# Esquematico.net
KiCad netlist of a schematic drawn in Altium Designer
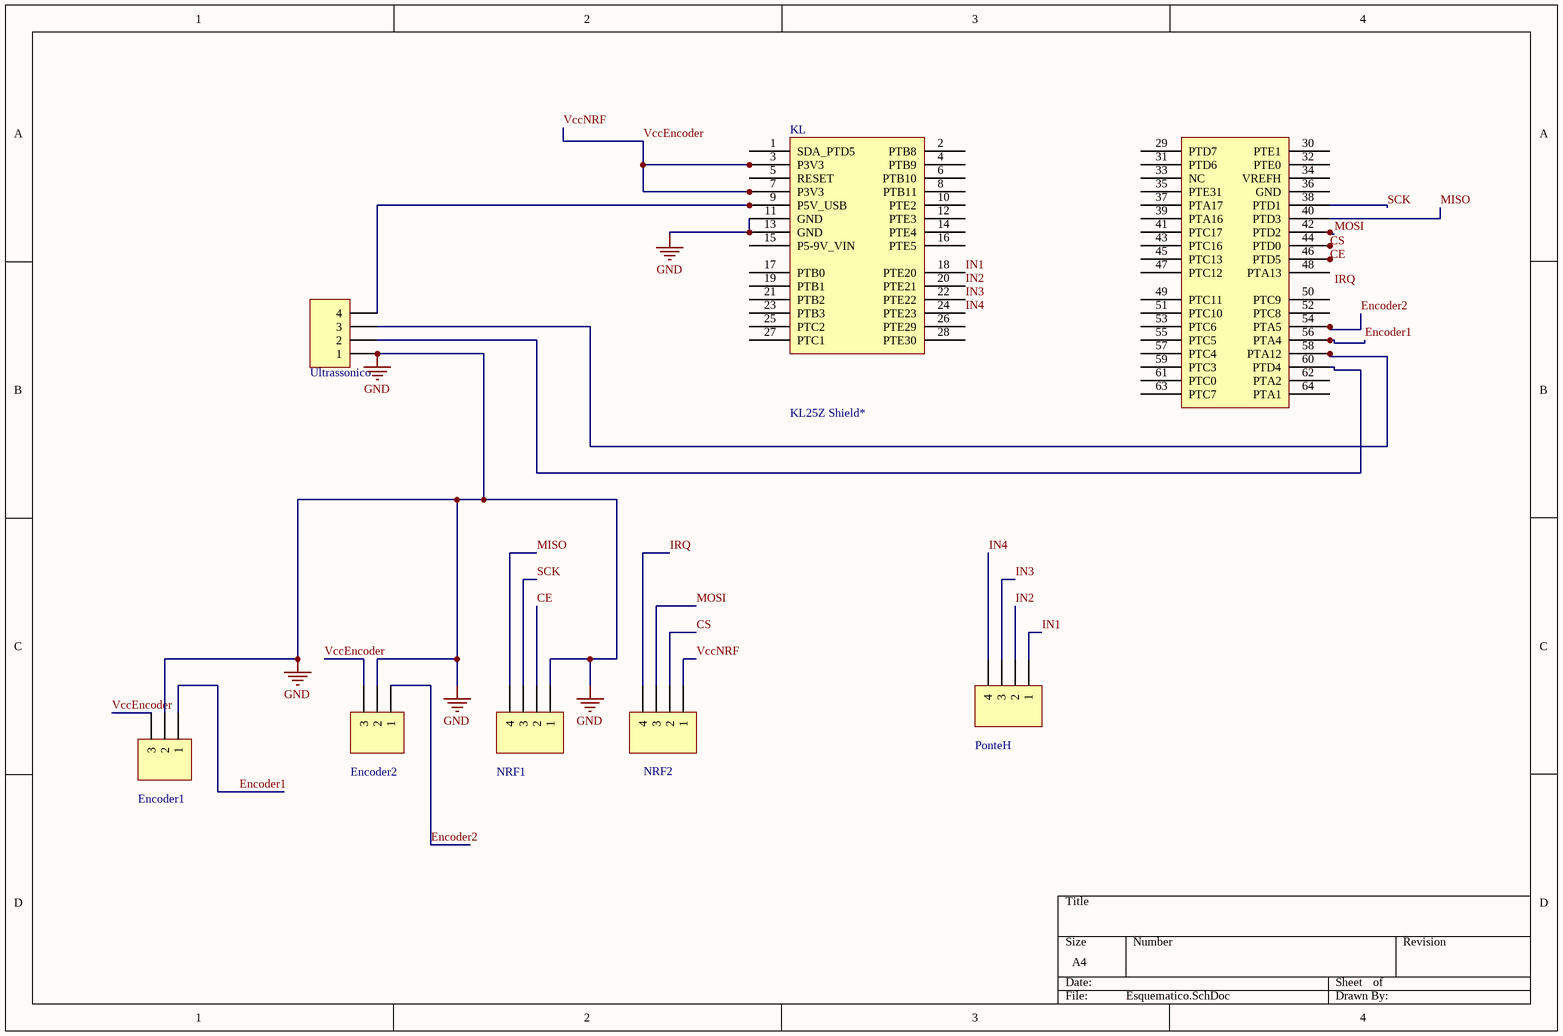
[diagram p0: Esquematico.SchDoc]

(export (version "E")
  (design (tool "Eeschema 10.0.6"))
  (components
    (comp (ref "Encoder1")
      (value "Header 1x3")
      (footprint "HDR FEMALE 1x3")
      (description "Headers & Wire Housings 40Pin 2mm Spacing Single Row Hdrs, 5pc")
      (fields (field (name "MANUFACTURER") "Cromax") (field (name "MANUFACTURER PART NUMBER") "IMP10327"))
      (libsource (lib "Schlib1") (part "Header 1x3"))
    )
    (comp (ref "Encoder2")
      (value "Header 1x3")
      (footprint "HDR FEMALE 1x3")
      (description "Headers & Wire Housings 40Pin 2mm Spacing Single Row Hdrs, 5pc")
      (fields (field (name "MANUFACTURER") "Cromax") (field (name "MANUFACTURER PART NUMBER") "IMP10327"))
      (libsource (lib "Schlib1") (part "Header 1x3"))
    )
    (comp (ref "KL")
      (value "KL25Z Shield*")
      (footprint "Freedom KL25Z Headerarray")
      (description "FRDM KL25Z Shield")
      (libsource (lib "Schlib1") (part "Freedom KL25Z Header"))
    )
    (comp (ref "NRF1")
      (value "Header Female 1x4")
      (footprint "HDR FEMALE 1x4")
      (description "Headers & Wire Housings 40Pin 2mm Spacing Single Row Hdrs, 5pc")
      (fields (field (name "MANUFACTURER") "Cromax"))
      (libsource (lib "Schlib1") (part "Header Female 1x4"))
    )
    (comp (ref "NRF2")
      (value "Header Female 1x4")
      (footprint "HDR FEMALE 1x4")
      (description "Headers & Wire Housings 40Pin 2mm Spacing Single Row Hdrs, 5pc")
      (fields (field (name "MANUFACTURER") "Cromax"))
      (libsource (lib "Schlib1") (part "Header Female 1x4"))
    )
    (comp (ref "PonteH")
      (value "Header Female 1x4")
      (footprint "HDR FEMALE 1x4")
      (description "Headers & Wire Housings 40Pin 2mm Spacing Single Row Hdrs, 5pc")
      (fields (field (name "MANUFACTURER") "Cromax"))
      (libsource (lib "Schlib1") (part "Header Female 1x4"))
    )
    (comp (ref "Ultrassonico")
      (value "Header Female 1x4")
      (footprint "HDR FEMALE 1x4")
      (description "Headers & Wire Housings 40Pin 2mm Spacing Single Row Hdrs, 5pc")
      (fields (field (name "MANUFACTURER") "Cromax"))
      (libsource (lib "") (part "Header Female 1x4_1"))
    )
  )
  (nets
    (net (code "1") (name "/CE") (class "Default")
      (node (ref "KL") (pin "46") (pinfunction "PTD5_46") (pintype "passive"))
      (node (ref "NRF1") (pin "2") (pinfunction "2_2") (pintype "passive"))
    )
    (net (code "2") (name "/CS") (class "Default")
      (node (ref "KL") (pin "44") (pinfunction "PTD0_44") (pintype "passive"))
      (node (ref "NRF2") (pin "2") (pinfunction "2_2") (pintype "passive"))
    )
    (net (code "3") (name "/Encoder1") (class "Default")
      (node (ref "Encoder1") (pin "1") (pinfunction "1_1") (pintype "passive"))
      (node (ref "KL") (pin "56") (pinfunction "PTA4_56") (pintype "passive"))
    )
    (net (code "4") (name "/Encoder2") (class "Default")
      (node (ref "Encoder2") (pin "1") (pinfunction "1_1") (pintype "passive"))
      (node (ref "KL") (pin "54") (pinfunction "PTA5_54") (pintype "passive"))
    )
    (net (code "5") (name "/IN1") (class "Default")
      (node (ref "KL") (pin "18") (pinfunction "PTE20_18") (pintype "passive"))
      (node (ref "PonteH") (pin "1") (pinfunction "1_1") (pintype "passive"))
    )
    (net (code "6") (name "/IN2") (class "Default")
      (node (ref "KL") (pin "20") (pinfunction "PTE21_20") (pintype "passive"))
      (node (ref "PonteH") (pin "2") (pinfunction "2_2") (pintype "passive"))
    )
    (net (code "7") (name "/IN3") (class "Default")
      (node (ref "KL") (pin "22") (pinfunction "PTE22_22") (pintype "passive"))
      (node (ref "PonteH") (pin "3") (pinfunction "3_3") (pintype "power_in"))
    )
    (net (code "8") (name "/IN4") (class "Default")
      (node (ref "KL") (pin "24") (pinfunction "PTE23_24") (pintype "passive"))
      (node (ref "PonteH") (pin "4") (pinfunction "4_4") (pintype "power_in"))
    )
    (net (code "9") (name "/IRQ") (class "Default")
      (node (ref "NRF2") (pin "4") (pinfunction "4_4") (pintype "power_in"))
    )
    (net (code "10") (name "/MISO") (class "Default")
      (node (ref "KL") (pin "40") (pinfunction "PTD3_40") (pintype "passive"))
      (node (ref "NRF1") (pin "4") (pinfunction "4_4") (pintype "power_in"))
    )
    (net (code "11") (name "/MOSI") (class "Default")
      (node (ref "KL") (pin "42") (pinfunction "PTD2_42") (pintype "passive"))
      (node (ref "NRF2") (pin "3") (pinfunction "3_3") (pintype "power_in"))
    )
    (net (code "12") (name "/SCK") (class "Default")
      (node (ref "KL") (pin "38") (pinfunction "PTD1_38") (pintype "passive"))
      (node (ref "NRF1") (pin "3") (pinfunction "3_3") (pintype "power_in"))
    )
    (net (code "13") (name "/VccEncoder") (class "Default")
      (node (ref "Encoder1") (pin "3") (pinfunction "3_3") (pintype "power_in"))
      (node (ref "Encoder2") (pin "3") (pinfunction "3_3") (pintype "power_in"))
      (node (ref "KL") (pin "3") (pinfunction "P3V3_3") (pintype "passive"))
      (node (ref "KL") (pin "7") (pinfunction "P3V3_7") (pintype "passive"))
      (node (ref "NRF2") (pin "1") (pinfunction "1_1") (pintype "passive"))
    )
    (net (code "14") (name "GND") (class "Default")
      (node (ref "Encoder1") (pin "2") (pinfunction "2_2") (pintype "passive"))
      (node (ref "Encoder2") (pin "2") (pinfunction "2_2") (pintype "passive"))
      (node (ref "KL") (pin "11") (pinfunction "GND_11") (pintype "passive"))
      (node (ref "KL") (pin "13") (pinfunction "GND_13") (pintype "passive"))
      (node (ref "NRF1") (pin "1") (pinfunction "1_1") (pintype "passive"))
      (node (ref "Ultrassonico") (pin "1") (pinfunction "1_1") (pintype "passive"))
    )
    (net (code "15") (name "Net-(KL-P5V_USB)") (class "Default")
      (node (ref "KL") (pin "9") (pinfunction "P5V_USB_9") (pintype "passive"))
      (node (ref "Ultrassonico") (pin "4") (pinfunction "4_4") (pintype "power_in"))
    )
    (net (code "16") (name "Net-(KL-PTA12)") (class "Default")
      (node (ref "KL") (pin "58") (pinfunction "PTA12_58") (pintype "passive"))
      (node (ref "Ultrassonico") (pin "3") (pinfunction "3_3") (pintype "power_in"))
    )
    (net (code "17") (name "Net-(KL-PTD4)") (class "Default")
      (node (ref "KL") (pin "60") (pinfunction "PTD4_60") (pintype "passive"))
      (node (ref "Ultrassonico") (pin "2") (pinfunction "2_2") (pintype "passive"))
    )
    (net (code "18") (name "unconnected-(KL-GND-Pad36)") (class "Default")
      (node (ref "KL") (pin "36") (pinfunction "GND_36") (pintype "passive"))
    )
    (net (code "19") (name "unconnected-(KL-NC-Pad33)") (class "Default")
      (node (ref "KL") (pin "33") (pinfunction "NC_33") (pintype "passive"))
    )
    (net (code "20") (name "unconnected-(KL-P5-9V_VIN-Pad15)") (class "Default")
      (node (ref "KL") (pin "15") (pinfunction "P5-9V_VIN_15") (pintype "passive"))
    )
    (net (code "21") (name "unconnected-(KL-PTA1-Pad64)") (class "Default")
      (node (ref "KL") (pin "64") (pinfunction "PTA1_64") (pintype "passive"))
    )
    (net (code "22") (name "unconnected-(KL-PTA2-Pad62)") (class "Default")
      (node (ref "KL") (pin "62") (pinfunction "PTA2_62") (pintype "passive"))
    )
    (net (code "23") (name "unconnected-(KL-PTA13-Pad48)") (class "Default")
      (node (ref "KL") (pin "48") (pinfunction "PTA13_48") (pintype "passive"))
    )
    (net (code "24") (name "unconnected-(KL-PTA16-Pad39)") (class "Default")
      (node (ref "KL") (pin "39") (pinfunction "PTA16_39") (pintype "passive"))
    )
    (net (code "25") (name "unconnected-(KL-PTA17-Pad37)") (class "Default")
      (node (ref "KL") (pin "37") (pinfunction "PTA17_37") (pintype "passive"))
    )
    (net (code "26") (name "unconnected-(KL-PTB0-Pad17)") (class "Default")
      (node (ref "KL") (pin "17") (pinfunction "PTB0_17") (pintype "passive"))
    )
    (net (code "27") (name "unconnected-(KL-PTB1-Pad19)") (class "Default")
      (node (ref "KL") (pin "19") (pinfunction "PTB1_19") (pintype "passive"))
    )
    (net (code "28") (name "unconnected-(KL-PTB2-Pad21)") (class "Default")
      (node (ref "KL") (pin "21") (pinfunction "PTB2_21") (pintype "passive"))
    )
    (net (code "29") (name "unconnected-(KL-PTB3-Pad23)") (class "Default")
      (node (ref "KL") (pin "23") (pinfunction "PTB3_23") (pintype "passive"))
    )
    (net (code "30") (name "unconnected-(KL-PTB8-Pad2)") (class "Default")
      (node (ref "KL") (pin "2") (pinfunction "PTB8_2") (pintype "passive"))
    )
    (net (code "31") (name "unconnected-(KL-PTB9-Pad4)") (class "Default")
      (node (ref "KL") (pin "4") (pinfunction "PTB9_4") (pintype "passive"))
    )
    (net (code "32") (name "unconnected-(KL-PTB10-Pad6)") (class "Default")
      (node (ref "KL") (pin "6") (pinfunction "PTB10_6") (pintype "passive"))
    )
    (net (code "33") (name "unconnected-(KL-PTB11-Pad8)") (class "Default")
      (node (ref "KL") (pin "8") (pinfunction "PTB11_8") (pintype "passive"))
    )
    (net (code "34") (name "unconnected-(KL-PTC0-Pad61)") (class "Default")
      (node (ref "KL") (pin "61") (pinfunction "PTC0_61") (pintype "passive"))
    )
    (net (code "35") (name "unconnected-(KL-PTC1-Pad27)") (class "Default")
      (node (ref "KL") (pin "27") (pinfunction "PTC1_27") (pintype "passive"))
    )
    (net (code "36") (name "unconnected-(KL-PTC2-Pad25)") (class "Default")
      (node (ref "KL") (pin "25") (pinfunction "PTC2_25") (pintype "passive"))
    )
    (net (code "37") (name "unconnected-(KL-PTC3-Pad59)") (class "Default")
      (node (ref "KL") (pin "59") (pinfunction "PTC3_59") (pintype "passive"))
    )
    (net (code "38") (name "unconnected-(KL-PTC4-Pad57)") (class "Default")
      (node (ref "KL") (pin "57") (pinfunction "PTC4_57") (pintype "passive"))
    )
    (net (code "39") (name "unconnected-(KL-PTC5-Pad55)") (class "Default")
      (node (ref "KL") (pin "55") (pinfunction "PTC5_55") (pintype "passive"))
    )
    (net (code "40") (name "unconnected-(KL-PTC6-Pad53)") (class "Default")
      (node (ref "KL") (pin "53") (pinfunction "PTC6_53") (pintype "passive"))
    )
    (net (code "41") (name "unconnected-(KL-PTC7-Pad63)") (class "Default")
      (node (ref "KL") (pin "63") (pinfunction "PTC7_63") (pintype "passive"))
    )
    (net (code "42") (name "unconnected-(KL-PTC8-Pad52)") (class "Default")
      (node (ref "KL") (pin "52") (pinfunction "PTC8_52") (pintype "passive"))
    )
    (net (code "43") (name "unconnected-(KL-PTC9-Pad50)") (class "Default")
      (node (ref "KL") (pin "50") (pinfunction "PTC9_50") (pintype "passive"))
    )
    (net (code "44") (name "unconnected-(KL-PTC10-Pad51)") (class "Default")
      (node (ref "KL") (pin "51") (pinfunction "PTC10_51") (pintype "passive"))
    )
    (net (code "45") (name "unconnected-(KL-PTC11-Pad49)") (class "Default")
      (node (ref "KL") (pin "49") (pinfunction "PTC11_49") (pintype "passive"))
    )
    (net (code "46") (name "unconnected-(KL-PTC12-Pad47)") (class "Default")
      (node (ref "KL") (pin "47") (pinfunction "PTC12_47") (pintype "passive"))
    )
    (net (code "47") (name "unconnected-(KL-PTC13-Pad45)") (class "Default")
      (node (ref "KL") (pin "45") (pinfunction "PTC13_45") (pintype "passive"))
    )
    (net (code "48") (name "unconnected-(KL-PTC16-Pad43)") (class "Default")
      (node (ref "KL") (pin "43") (pinfunction "PTC16_43") (pintype "passive"))
    )
    (net (code "49") (name "unconnected-(KL-PTC17-Pad41)") (class "Default")
      (node (ref "KL") (pin "41") (pinfunction "PTC17_41") (pintype "passive"))
    )
    (net (code "50") (name "unconnected-(KL-PTD6-Pad31)") (class "Default")
      (node (ref "KL") (pin "31") (pinfunction "PTD6_31") (pintype "passive"))
    )
    (net (code "51") (name "unconnected-(KL-PTD7-Pad29)") (class "Default")
      (node (ref "KL") (pin "29") (pinfunction "PTD7_29") (pintype "passive"))
    )
    (net (code "52") (name "unconnected-(KL-PTE0-Pad32)") (class "Default")
      (node (ref "KL") (pin "32") (pinfunction "PTE0_32") (pintype "passive"))
    )
    (net (code "53") (name "unconnected-(KL-PTE1-Pad30)") (class "Default")
      (node (ref "KL") (pin "30") (pinfunction "PTE1_30") (pintype "passive"))
    )
    (net (code "54") (name "unconnected-(KL-PTE2-Pad10)") (class "Default")
      (node (ref "KL") (pin "10") (pinfunction "PTE2_10") (pintype "passive"))
    )
    (net (code "55") (name "unconnected-(KL-PTE3-Pad12)") (class "Default")
      (node (ref "KL") (pin "12") (pinfunction "PTE3_12") (pintype "passive"))
    )
    (net (code "56") (name "unconnected-(KL-PTE4-Pad14)") (class "Default")
      (node (ref "KL") (pin "14") (pinfunction "PTE4_14") (pintype "passive"))
    )
    (net (code "57") (name "unconnected-(KL-PTE5-Pad16)") (class "Default")
      (node (ref "KL") (pin "16") (pinfunction "PTE5_16") (pintype "passive"))
    )
    (net (code "58") (name "unconnected-(KL-PTE29-Pad26)") (class "Default")
      (node (ref "KL") (pin "26") (pinfunction "PTE29_26") (pintype "passive"))
    )
    (net (code "59") (name "unconnected-(KL-PTE30-Pad28)") (class "Default")
      (node (ref "KL") (pin "28") (pinfunction "PTE30_28") (pintype "passive"))
    )
    (net (code "60") (name "unconnected-(KL-PTE31-Pad35)") (class "Default")
      (node (ref "KL") (pin "35") (pinfunction "PTE31_35") (pintype "passive"))
    )
    (net (code "61") (name "unconnected-(KL-RESET-Pad5)") (class "Default")
      (node (ref "KL") (pin "5") (pinfunction "RESET_5") (pintype "passive"))
    )
    (net (code "62") (name "unconnected-(KL-SDA_PTD5-Pad1)") (class "Default")
      (node (ref "KL") (pin "1") (pinfunction "SDA_PTD5_1") (pintype "passive"))
    )
    (net (code "63") (name "unconnected-(KL-VREFH-Pad34)") (class "Default")
      (node (ref "KL") (pin "34") (pinfunction "VREFH_34") (pintype "passive"))
    )
  )
)
